# Ethernet_boardv3_09012016.net
KiCad netlist of a schematic drawn in Altium Designer
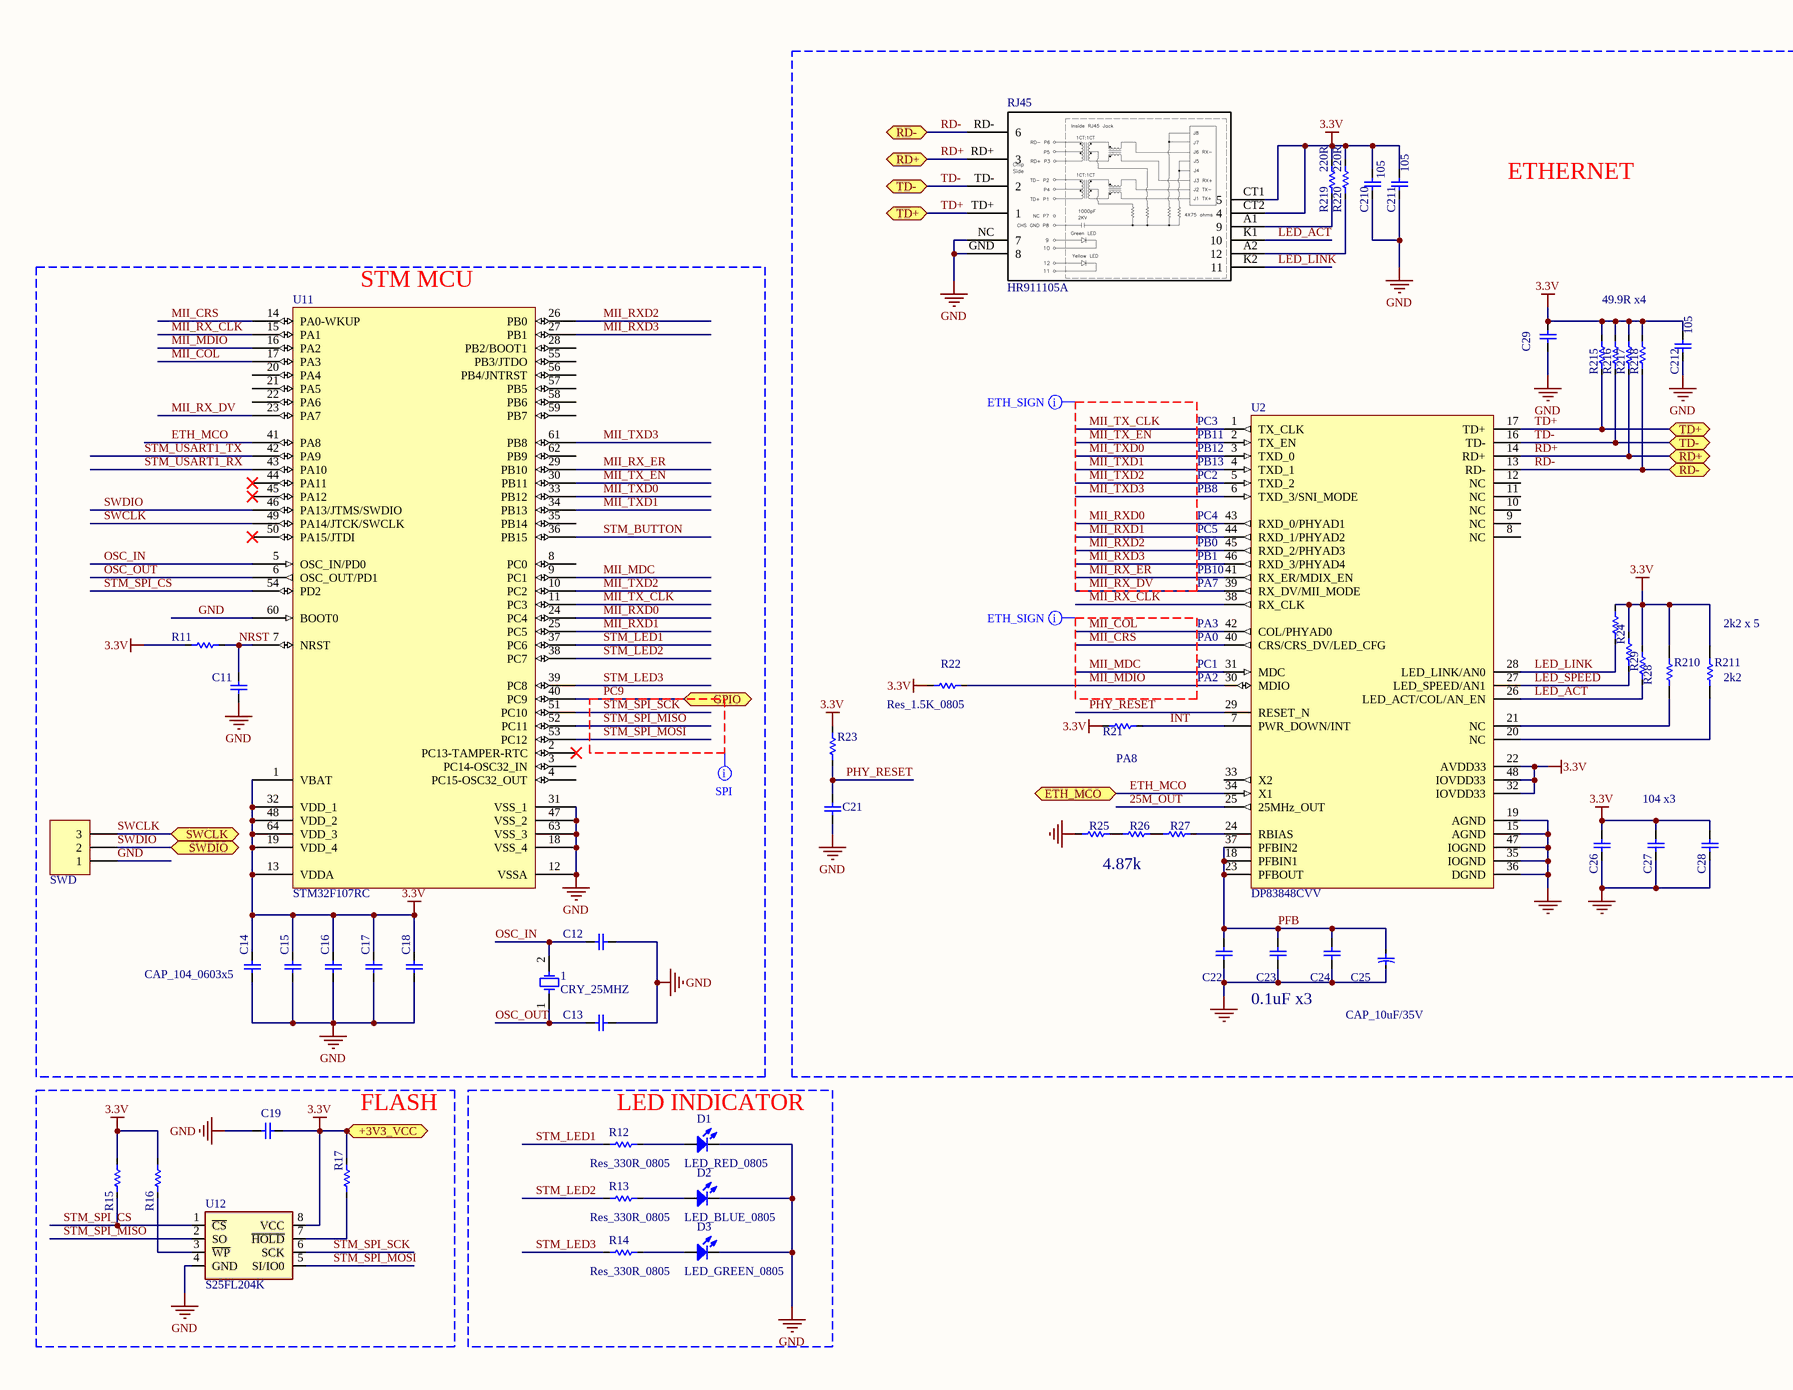
[diagram p0: Ethernet_boardv3_09012016.SchDoc, left]
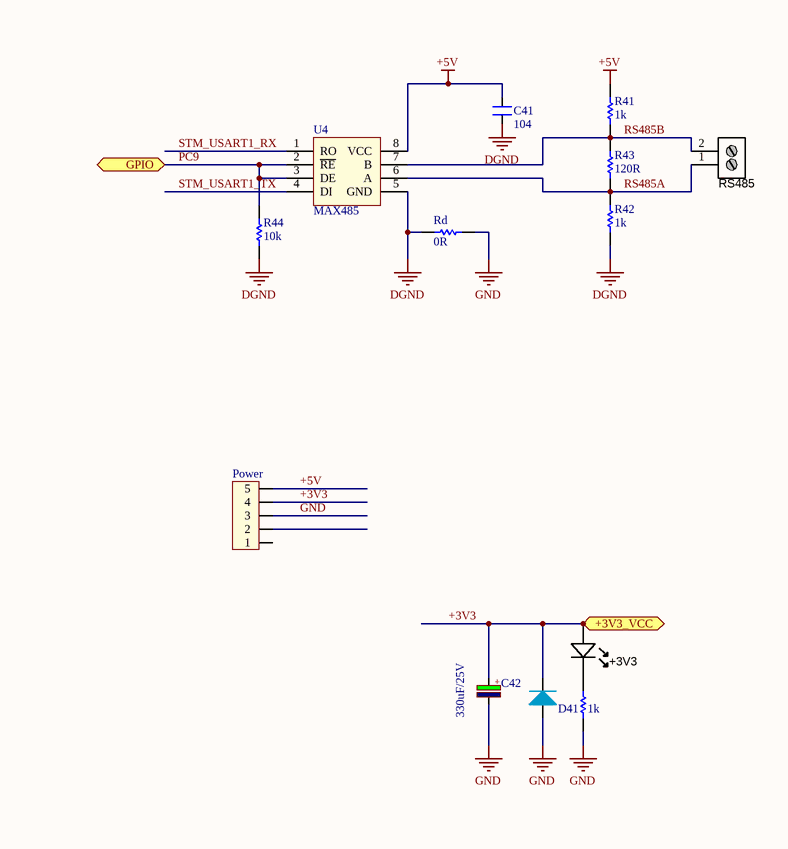
[diagram p1: Ethernet_boardv3_09012016.SchDoc, right]

(export (version "E")
  (design (tool "Eeschema 10.0.6"))
  (components
    (comp (ref "+3V3")
      (value "Blue")
      (footprint "LED-0805-K")
      (description "LED 0805 SMD Blue 100mcd 470nm")
      (libsource (lib "PBL - Light Sources") (part "LED_SMD_Blue_0805_100mcd"))
    )
    (comp (ref "1")
      (value "CRY_25MHZ")
      (footprint "XT2")
      (description "Crystal Oscillator")
      (fields (field (name "PUBLISHER") "Altium Limited"))
      (libsource (lib "THU VIEN CHAN") (part "cry"))
    )
    (comp (ref "C11")
      (value "CAP_102_0603")
      (footprint "CAP_0805_TOP")
      (description "Capacitor")
      (fields (field (name "PUBLISHER") "Altium Limited"))
      (libsource (lib "THU VIEN CHAN") (part "Cap 1206 BUT"))
    )
    (comp (ref "C12")
      (value "CAP_18pF_0603")
      (footprint "CAPC1608N_F")
      (description "Capacitor")
      (fields (field (name "PUBLISHER") "Altium Limited"))
      (libsource (lib "THU VIEN CHAN") (part "Cap 1206 BUT"))
    )
    (comp (ref "C13")
      (value "CAP_18pF_0603")
      (footprint "CAPC1608N_F")
      (description "Capacitor")
      (fields (field (name "PUBLISHER") "Altium Limited"))
      (libsource (lib "THU VIEN CHAN") (part "Cap 1206 BUT"))
    )
    (comp (ref "C14")
      (value "CAP_104_0603")
      (footprint "CAPC1608N_F")
      (description "Capacitor")
      (fields (field (name "PUBLISHER") "Altium Limited"))
      (libsource (lib "THU VIEN CHAN") (part "Cap 1206 BUT"))
    )
    (comp (ref "C15")
      (value "CAP_104_0603")
      (footprint "CAPC1608N_F")
      (description "Capacitor")
      (fields (field (name "PUBLISHER") "Altium Limited"))
      (libsource (lib "THU VIEN CHAN") (part "Cap 1206 BUT"))
    )
    (comp (ref "C16")
      (value "CAP_104_0603")
      (footprint "CAPC1608N_F")
      (description "Capacitor")
      (fields (field (name "PUBLISHER") "Altium Limited"))
      (libsource (lib "THU VIEN CHAN") (part "Cap 1206 BUT"))
    )
    (comp (ref "C17")
      (value "CAP_104_0603")
      (footprint "CAPC1608N_F")
      (description "Capacitor")
      (fields (field (name "PUBLISHER") "Altium Limited"))
      (libsource (lib "THU VIEN CHAN") (part "Cap 1206 BUT"))
    )
    (comp (ref "C18")
      (value "CAP_104_0603")
      (footprint "CAPC1608N_F")
      (description "Capacitor")
      (fields (field (name "PUBLISHER") "Altium Limited"))
      (libsource (lib "THU VIEN CHAN") (part "Cap 1206 BUT"))
    )
    (comp (ref "C19")
      (value "CAP_104_0603")
      (footprint "CAP_0805_TOP")
      (description "Capacitor")
      (fields (field (name "PUBLISHER") "Altium Limited"))
      (libsource (lib "THU VIEN CHAN") (part "Cap 1206 BUT"))
    )
    (comp (ref "C21")
      (value "CAP_102_0603")
      (footprint "CAPC1608N_F")
      (description "Capacitor")
      (fields (field (name "PUBLISHER") "Altium Limited"))
      (libsource (lib "THU VIEN CHAN") (part "Cap 1206 BUT"))
    )
    (comp (ref "C22")
      (value "CAP_104_0603")
      (footprint "CAPC1608N_F")
      (description "Capacitor")
      (fields (field (name "PUBLISHER") "Altium Limited"))
      (libsource (lib "THU VIEN CHAN") (part "Cap 1206 BUT"))
    )
    (comp (ref "C23")
      (value "CAP_104_0603")
      (footprint "CAPC1608N_F")
      (description "Capacitor")
      (fields (field (name "PUBLISHER") "Altium Limited"))
      (libsource (lib "THU VIEN CHAN") (part "Cap 1206 BUT"))
    )
    (comp (ref "C24")
      (value "CAP_104_0603")
      (footprint "CAPC1608N_F")
      (description "Capacitor")
      (fields (field (name "PUBLISHER") "Altium Limited"))
      (libsource (lib "THU VIEN CHAN") (part "Cap 1206 BUT"))
    )
    (comp (ref "C25")
      (value "CAP_10uF/35V")
      (footprint "CAP_10uF/35V")
      (fields (field (name "PUBLISHER") "Altium Limited"))
      (libsource (lib "THU VIEN CHAN") (part "CAP P"))
    )
    (comp (ref "C26")
      (value "CAP_104_0603")
      (footprint "CAPC1608N_F")
      (description "Capacitor")
      (fields (field (name "PUBLISHER") "Altium Limited"))
      (libsource (lib "THU VIEN CHAN") (part "Cap 1206 BUT"))
    )
    (comp (ref "C27")
      (value "CAP_104_0603")
      (footprint "CAPC1608N_F")
      (description "Capacitor")
      (fields (field (name "PUBLISHER") "Altium Limited"))
      (libsource (lib "THU VIEN CHAN") (part "Cap 1206 BUT"))
    )
    (comp (ref "C28")
      (value "CAP_104_0603")
      (footprint "CAPC1608N_F")
      (description "Capacitor")
      (fields (field (name "PUBLISHER") "Altium Limited"))
      (libsource (lib "THU VIEN CHAN") (part "Cap 1206 BUT"))
    )
    (comp (ref "C29")
      (value "CAP_104_0603")
      (footprint "CAPC2012N_F")
      (description "Capacitor")
      (fields (field (name "PUBLISHER") "Altium Limited"))
      (libsource (lib "THU VIEN CHAN") (part "Cap 1206 BUT"))
    )
    (comp (ref "C41")
      (value "104")
      (footprint "CAPC2012N_F")
      (fields (field (name "Comment") "100nF/104"))
      (libsource (lib "Tuan") (part "CAP NP"))
    )
    (comp (ref "C42")
      (value "330uF/25V")
      (footprint "CAPMP3528X210N")
      (description "Cap 1000uF/16V - 220uF/50V")
      (libsource (lib "heromap") (part "CP4"))
    )
    (comp (ref "C210")
      (value "105")
      (footprint "CAPC1608N_F")
      (description "Capacitor")
      (fields (field (name "PUBLISHER") "Altium Limited"))
      (libsource (lib "THU VIEN CHAN") (part "Cap 1206 BUT"))
    )
    (comp (ref "C211")
      (value "105")
      (footprint "CAPC1608N_F")
      (description "Capacitor")
      (fields (field (name "PUBLISHER") "Altium Limited"))
      (libsource (lib "THU VIEN CHAN") (part "Cap 1206 BUT"))
    )
    (comp (ref "C212")
      (value "105")
      (footprint "CAPC2012N_F")
      (description "Capacitor")
      (fields (field (name "PUBLISHER") "Altium Limited"))
      (libsource (lib "THU VIEN CHAN") (part "Cap 1206 BUT"))
    )
    (comp (ref "D1")
      (value "LED_RED_0805")
      (footprint "LED 0805 TOP")
      (description "Typical INFRARED GaAs LED")
      (fields (field (name "PUBLISHER") "Altium Limited"))
      (libsource (lib "THU VIEN CHAN v1") (part "LED 0805 TOP"))
    )
    (comp (ref "D2")
      (value "LED_BLUE_0805")
      (footprint "LED 0805 TOP")
      (description "Typical INFRARED GaAs LED")
      (fields (field (name "PUBLISHER") "Altium Limited"))
      (libsource (lib "THU VIEN CHAN v1") (part "LED 0805 TOP"))
    )
    (comp (ref "D3")
      (value "LED_GREEN_0805")
      (footprint "LED 0805 TOP")
      (description "Typical INFRARED GaAs LED")
      (fields (field (name "PUBLISHER") "Altium Limited"))
      (libsource (lib "THU VIEN CHAN v1") (part "LED 0805 TOP"))
    )
    (comp (ref "D41") (value "Diode") (footprint "DO-214AC") (libsource (lib "Tuan") (part "Diode")))
    (comp (ref "Power")
      (value "JP5")
      (footprint "heromap:CON5")
      (description "Connector 5")
      (libsource (lib "heromap") (part "Con5"))
    )
    (comp (ref "R11")
      (value "Res_4.7K_0805")
      (footprint "RES_0805_TOP")
      (description "Resistor")
      (fields (field (name "PUBLISHER") "Altium Limited"))
      (libsource (lib "THU VIEN CHAN") (part "Res"))
    )
    (comp (ref "R12")
      (value "Res_330R_0805")
      (footprint "RES_0805_TOP")
      (description "Resistor")
      (fields (field (name "PUBLISHER") "Altium Limited"))
      (libsource (lib "THU VIEN CHAN") (part "Res"))
    )
    (comp (ref "R13")
      (value "Res_330R_0805")
      (footprint "RES_0805_TOP")
      (description "Resistor")
      (fields (field (name "PUBLISHER") "Altium Limited"))
      (libsource (lib "THU VIEN CHAN") (part "Res"))
    )
    (comp (ref "R14")
      (value "Res_330R_0805")
      (footprint "RES_0805_TOP")
      (description "Resistor")
      (fields (field (name "PUBLISHER") "Altium Limited"))
      (libsource (lib "THU VIEN CHAN") (part "Res"))
    )
    (comp (ref "R15")
      (value "Res_4.7K_0805")
      (footprint "RES_0805_TOP")
      (description "Resistor")
      (fields (field (name "PUBLISHER") "Altium Limited"))
      (libsource (lib "THU VIEN CHAN") (part "Res"))
    )
    (comp (ref "R16")
      (value "Res_4.7K_0805")
      (footprint "RES_0805_TOP")
      (description "Resistor")
      (fields (field (name "PUBLISHER") "Altium Limited"))
      (libsource (lib "THU VIEN CHAN") (part "Res"))
    )
    (comp (ref "R17")
      (value "Res_4.7K_0805")
      (footprint "RES_0805_TOP")
      (description "Resistor")
      (fields (field (name "PUBLISHER") "Altium Limited"))
      (libsource (lib "THU VIEN CHAN") (part "Res"))
    )
    (comp (ref "R21")
      (value "Res_2.2K_0805")
      (footprint "RESC1608N_F")
      (description "Resistor")
      (fields (field (name "PUBLISHER") "Altium Limited"))
      (libsource (lib "THU VIEN CHAN") (part "Res"))
    )
    (comp (ref "R22")
      (value "Res_1.5K_0805")
      (footprint "RESC1608N_F")
      (description "Resistor")
      (fields (field (name "PUBLISHER") "Altium Limited"))
      (libsource (lib "") (part "Res_1"))
    )
    (comp (ref "R23")
      (value "Res_4.7K_0805")
      (footprint "RESC1608N_F")
      (description "Resistor")
      (fields (field (name "PUBLISHER") "Altium Limited"))
      (libsource (lib "") (part "Res_1"))
    )
    (comp (ref "R24")
      (value "Res_2.2K_0805")
      (footprint "RESC1608N_F")
      (description "Resistor")
      (fields (field (name "PUBLISHER") "Altium Limited"))
      (libsource (lib "THU VIEN CHAN") (part "Res"))
    )
    (comp (ref "R25")
      (value "Res_47R_0805")
      (footprint "RES_0805_TOP")
      (description "Resistor")
      (fields (field (name "PUBLISHER") "Altium Limited"))
      (libsource (lib "THU VIEN CHAN") (part "Res"))
    )
    (comp (ref "R26")
      (value "Res_120R_0805")
      (footprint "RES_0805_TOP")
      (description "Resistor")
      (fields (field (name "PUBLISHER") "Altium Limited"))
      (libsource (lib "THU VIEN CHAN") (part "Res"))
    )
    (comp (ref "R27")
      (value "Res_4.7K_0805")
      (footprint "RES_0805_TOP")
      (description "Resistor")
      (fields (field (name "PUBLISHER") "Altium Limited"))
      (libsource (lib "THU VIEN CHAN") (part "Res"))
    )
    (comp (ref "R28")
      (value "Res_0R_0603")
      (footprint "RESC1608N_F")
      (description "Resistor")
      (fields (field (name "PUBLISHER") "Altium Limited"))
      (libsource (lib "THU VIEN CHAN") (part "Res"))
    )
    (comp (ref "R29")
      (value "Res_0R_0603")
      (footprint "RESC1608N_F")
      (description "Resistor")
      (fields (field (name "PUBLISHER") "Altium Limited"))
      (libsource (lib "THU VIEN CHAN") (part "Res"))
    )
    (comp (ref "R41")
      (value "1k")
      (footprint "RESC2012N_F")
      (description "Tro dan")
      (libsource (lib "GPS_Clock_v12") (part "Res"))
    )
    (comp (ref "R42")
      (value "1k")
      (footprint "RESC2012N_F")
      (description "Tro dan")
      (libsource (lib "GPS_Clock_v12") (part "Res"))
    )
    (comp (ref "R43")
      (value "120R")
      (footprint "RESC2012N_F")
      (description "Tro dan")
      (fields (field (name "Comment") "330R"))
      (libsource (lib "GPS_Clock_v12") (part "Res"))
    )
    (comp (ref "R44")
      (value "10k")
      (footprint "RESC2012N_F")
      (description "Tro dan")
      (fields (field (name "Comment") "330R"))
      (libsource (lib "GPS_Clock_v12") (part "Res"))
    )
    (comp (ref "R210") (value "2k2") (footprint "RESC1608N_F") (libsource (lib "Tuan") (part "Res")))
    (comp (ref "R211") (value "2k2") (footprint "RESC1608N_F") (libsource (lib "Tuan") (part "Res")))
    (comp (ref "R215")
      (value "Res_49.9R_0805")
      (footprint "RES_0805_TOP")
      (description "Resistor")
      (fields (field (name "PUBLISHER") "Altium Limited"))
      (libsource (lib "THU VIEN CHAN") (part "Res"))
    )
    (comp (ref "R216")
      (value "Res_49.9R_0805")
      (footprint "RES_0805_TOP")
      (description "Resistor")
      (fields (field (name "PUBLISHER") "Altium Limited"))
      (libsource (lib "THU VIEN CHAN") (part "Res"))
    )
    (comp (ref "R217")
      (value "Res_49.9R_0805")
      (footprint "RES_0805_TOP")
      (description "Resistor")
      (fields (field (name "PUBLISHER") "Altium Limited"))
      (libsource (lib "THU VIEN CHAN") (part "Res"))
    )
    (comp (ref "R218")
      (value "Res_49.9R_0805")
      (footprint "RES_0805_TOP")
      (description "Resistor")
      (fields (field (name "PUBLISHER") "Altium Limited"))
      (libsource (lib "THU VIEN CHAN") (part "Res"))
    )
    (comp (ref "R219")
      (value "220R")
      (footprint "RESC1608N_F")
      (description "Resistor")
      (fields (field (name "PUBLISHER") "Altium Limited"))
      (libsource (lib "THU VIEN CHAN") (part "Res"))
    )
    (comp (ref "R220")
      (value "220R")
      (footprint "RESC1608N_F")
      (description "Resistor")
      (fields (field (name "PUBLISHER") "Altium Limited"))
      (libsource (lib "THU VIEN CHAN") (part "Res"))
    )
    (comp (ref "Rd")
      (value "0R")
      (footprint "RESC2012N_F")
      (fields (field (name "Comment") "Res"))
      (libsource (lib "Tuan") (part "Res"))
    )
    (comp (ref "RJ45") (value "HR911105A") (footprint "HR911105A") (libsource (lib "Tuan") (part "RJ45-LED")))
    (comp (ref "Rled")
      (value "1k")
      (footprint "RESC2012N_F")
      (fields (field (name "Comment") "Res_0805_1k"))
      (libsource (lib "Tuan") (part "Res"))
    )
    (comp (ref "RS485")
      (value "Stackable ScrewTerm")
      (footprint "2P_PCB1")
      (description "Terminal Block Screw Type THT 2-Position 3.81mm pitch")
      (libsource (lib "PBL - Connectors") (part "2P_ScrewTerm_90S_3.81MM"))
    )
    (comp (ref "SWD")
      (value "Header 3")
      (footprint "heromap:HDR1X3")
      (description "Header, 3-Pin")
      (fields (field (name "PUBLISHER") "Altium Limited"))
      (libsource (lib "heromap") (part "Header 3"))
    )
    (comp (ref "U2")
      (value "DP83848CVV")
      (footprint "LQFP48")
      (libsource (lib "THU VIEN CHAN v1") (part "DP83848CVV"))
    )
    (comp (ref "U4")
      (value "MAX485")
      (footprint "SO-8")
      (description "RS232 - RS485 (Same sn75176)")
      (libsource (lib "heromap") (part "MAX485"))
    )
    (comp (ref "U11")
      (value "STM32F107RC")
      (footprint "LQFP64_N")
      (description "STM32 ARM-based 32-bit MCU with 128 Kbytes Flash, 64-pin LQFP, Industrial Temperature")
      (fields (field (name "PUBLISHER") "Altium Limited"))
      (libsource (lib "ST Microcontroller 32-Bit STM32") (part "STM32F103RBT6"))
    )
    (comp (ref "U12")
      (value "S25FL204K")
      (footprint "SOIC_8")
      (libsource (lib "THU VIEN CHAN v1") (part "S25FL204K"))
    )
  )
  (nets
    (net (code "1") (name "+5V") (class "Default")
      (node (ref "C41") (pin "2") (pinfunction "2_2") (pintype "passive"))
      (node (ref "Power") (pin "5") (pinfunction "5_5") (pintype "passive"))
      (node (ref "R41") (pin "2") (pinfunction "2_2") (pintype "passive"))
      (node (ref "U4") (pin "8") (pinfunction "VCC_8") (pintype "passive"))
    )
    (net (code "2") (name "/25M_OUT") (class "Default")
      (node (ref "U2") (pin "25") (pinfunction "25MHz_OUT_25") (pintype "output"))
    )
    (net (code "3") (name "/ETH_MCO") (class "Default")
      (node (ref "U11") (pin "41") (pinfunction "PA8_41") (pintype "bidirectional"))
      (node (ref "U2") (pin "34") (pinfunction "X1_34") (pintype "input"))
    )
    (net (code "4") (name "/INT") (class "Default")
      (node (ref "R21") (pin "1") (pinfunction "1_1") (pintype "passive"))
      (node (ref "U2") (pin "7") (pinfunction "PWR_DOWN/INT_7") (pintype "passive"))
    )
    (net (code "5") (name "/LED_ACT") (class "Default")
      (node (ref "R28") (pin "2") (pinfunction "2_2") (pintype "passive"))
      (node (ref "RJ45") (pin "K1") (pinfunction "10_K1") (pintype "passive"))
      (node (ref "U2") (pin "26") (pinfunction "LED_ACT/COL/AN_EN_26") (pintype "passive"))
    )
    (net (code "6") (name "/LED_LINK") (class "Default")
      (node (ref "R24") (pin "1") (pinfunction "1_1") (pintype "passive"))
      (node (ref "RJ45") (pin "K2") (pinfunction "11_K2") (pintype "passive"))
      (node (ref "U2") (pin "28") (pinfunction "LED_LINK/AN0_28") (pintype "passive"))
    )
    (net (code "7") (name "/LED_SPEED") (class "Default")
      (node (ref "R29") (pin "1") (pinfunction "1_1") (pintype "passive"))
      (node (ref "U2") (pin "27") (pinfunction "LED_SPEED/AN1_27") (pintype "passive"))
    )
    (net (code "8") (name "/MII_COL") (class "Default")
      (node (ref "U11") (pin "17") (pinfunction "PA3_17") (pintype "bidirectional"))
      (node (ref "U2") (pin "42") (pinfunction "COL/PHYAD0_42") (pintype "output"))
    )
    (net (code "9") (name "/MII_CRS") (class "Default")
      (node (ref "U11") (pin "14") (pinfunction "PA0-WKUP_14") (pintype "bidirectional"))
      (node (ref "U2") (pin "40") (pinfunction "CRS/CRS_DV/LED_CFG_40") (pintype "output"))
    )
    (net (code "10") (name "/MII_MDC") (class "Default")
      (node (ref "U11") (pin "9") (pinfunction "PC1_9") (pintype "bidirectional"))
      (node (ref "U2") (pin "31") (pinfunction "MDC_31") (pintype "input"))
    )
    (net (code "11") (name "/MII_MDIO") (class "Default")
      (node (ref "R22") (pin "2") (pinfunction "2_2") (pintype "passive"))
      (node (ref "U11") (pin "16") (pinfunction "PA2_16") (pintype "bidirectional"))
      (node (ref "U2") (pin "30") (pinfunction "MDIO_30") (pintype "bidirectional"))
    )
    (net (code "12") (name "/MII_RXD0") (class "Default")
      (node (ref "U11") (pin "24") (pinfunction "PC4_24") (pintype "bidirectional"))
      (node (ref "U2") (pin "43") (pinfunction "RXD_0/PHYAD1_43") (pintype "output"))
    )
    (net (code "13") (name "/MII_RXD1") (class "Default")
      (node (ref "U11") (pin "25") (pinfunction "PC5_25") (pintype "bidirectional"))
      (node (ref "U2") (pin "44") (pinfunction "RXD_1/PHYAD2_44") (pintype "output"))
    )
    (net (code "14") (name "/MII_RXD2") (class "Default")
      (node (ref "U11") (pin "26") (pinfunction "PB0_26") (pintype "bidirectional"))
      (node (ref "U2") (pin "45") (pinfunction "RXD_2/PHYAD3_45") (pintype "output"))
    )
    (net (code "15") (name "/MII_RXD3") (class "Default")
      (node (ref "U11") (pin "27") (pinfunction "PB1_27") (pintype "bidirectional"))
      (node (ref "U2") (pin "46") (pinfunction "RXD_3/PHYAD4_46") (pintype "output"))
    )
    (net (code "16") (name "/MII_RX_CLK") (class "Default")
      (node (ref "U11") (pin "15") (pinfunction "PA1_15") (pintype "bidirectional"))
      (node (ref "U2") (pin "38") (pinfunction "RX_CLK_38") (pintype "output"))
    )
    (net (code "17") (name "/MII_RX_DV") (class "Default")
      (node (ref "U11") (pin "23") (pinfunction "PA7_23") (pintype "bidirectional"))
      (node (ref "U2") (pin "39") (pinfunction "RX_DV/MII_MODE_39") (pintype "output"))
    )
    (net (code "18") (name "/MII_RX_ER") (class "Default")
      (node (ref "U11") (pin "29") (pinfunction "PB10_29") (pintype "bidirectional"))
      (node (ref "U2") (pin "41") (pinfunction "RX_ER/MDIX_EN_41") (pintype "output"))
    )
    (net (code "19") (name "/MII_TXD0") (class "Default")
      (node (ref "U11") (pin "33") (pinfunction "PB12_33") (pintype "bidirectional"))
      (node (ref "U2") (pin "3") (pinfunction "TXD_0_3") (pintype "input"))
    )
    (net (code "20") (name "/MII_TXD1") (class "Default")
      (node (ref "U11") (pin "34") (pinfunction "PB13_34") (pintype "bidirectional"))
      (node (ref "U2") (pin "4") (pinfunction "TXD_1_4") (pintype "input"))
    )
    (net (code "21") (name "/MII_TXD2") (class "Default")
      (node (ref "U11") (pin "10") (pinfunction "PC2_10") (pintype "bidirectional"))
      (node (ref "U2") (pin "5") (pinfunction "TXD_2_5") (pintype "input"))
    )
    (net (code "22") (name "/MII_TXD3") (class "Default")
      (node (ref "U11") (pin "61") (pinfunction "PB8_61") (pintype "bidirectional"))
      (node (ref "U2") (pin "6") (pinfunction "TXD_3/SNI_MODE_6") (pintype "input"))
    )
    (net (code "23") (name "/MII_TX_CLK") (class "Default")
      (node (ref "U11") (pin "11") (pinfunction "PC3_11") (pintype "bidirectional"))
      (node (ref "U2") (pin "1") (pinfunction "TX_CLK_1") (pintype "output"))
    )
    (net (code "24") (name "/MII_TX_EN") (class "Default")
      (node (ref "U11") (pin "30") (pinfunction "PB11_30") (pintype "bidirectional"))
      (node (ref "U2") (pin "2") (pinfunction "TX_EN_2") (pintype "input"))
    )
    (net (code "25") (name "/NRST") (class "Default")
      (node (ref "C11") (pin "1") (pinfunction "1_1") (pintype "passive"))
      (node (ref "R11") (pin "1") (pinfunction "1_1") (pintype "passive"))
      (node (ref "U11") (pin "7") (pinfunction "NRST_7") (pintype "bidirectional"))
    )
    (net (code "26") (name "/OSC_IN") (class "Default")
      (node (ref "1") (pin "2") (pinfunction "OSC2_2") (pintype "passive"))
      (node (ref "C12") (pin "1") (pinfunction "1_1") (pintype "passive"))
      (node (ref "U11") (pin "5") (pinfunction "OSC_IN/PD0_5") (pintype "input"))
    )
    (net (code "27") (name "/OSC_OUT") (class "Default")
      (node (ref "1") (pin "1") (pinfunction "OSC1_1") (pintype "passive"))
      (node (ref "C13") (pin "1") (pinfunction "1_1") (pintype "passive"))
      (node (ref "U11") (pin "6") (pinfunction "OSC_OUT/PD1_6") (pintype "output"))
    )
    (net (code "28") (name "/PC9") (class "Default")
      (node (ref "R44") (pin "2") (pinfunction "2_2") (pintype "passive"))
      (node (ref "U11") (pin "40") (pinfunction "PC9_40") (pintype "bidirectional"))
      (node (ref "U4") (pin "2") (pinfunction "~{RE}_2") (pintype "passive"))
      (node (ref "U4") (pin "3") (pinfunction "DE_3") (pintype "passive"))
    )
    (net (code "29") (name "/PFB") (class "Default")
      (node (ref "C22") (pin "2") (pinfunction "2_2") (pintype "passive"))
      (node (ref "C23") (pin "2") (pinfunction "2_2") (pintype "passive"))
      (node (ref "C24") (pin "2") (pinfunction "2_2") (pintype "passive"))
      (node (ref "C25") (pin "1") (pinfunction "1_1") (pintype "passive"))
      (node (ref "U2") (pin "18") (pinfunction "PFBIN1_18") (pintype "passive"))
      (node (ref "U2") (pin "23") (pinfunction "PFBOUT_23") (pintype "passive"))
      (node (ref "U2") (pin "37") (pinfunction "PFBIN2_37") (pintype "passive"))
    )
    (net (code "30") (name "/PHY_RESET") (class "Default")
      (node (ref "C21") (pin "2") (pinfunction "2_2") (pintype "passive"))
      (node (ref "R23") (pin "1") (pinfunction "1_1") (pintype "passive"))
      (node (ref "U2") (pin "29") (pinfunction "RESET_N_29") (pintype "passive"))
    )
    (net (code "31") (name "/RD+") (class "Default")
      (node (ref "R217") (pin "2") (pinfunction "2_2") (pintype "passive"))
      (node (ref "RJ45") (pin "RD+") (pinfunction "3_RD+") (pintype "passive"))
      (node (ref "U2") (pin "14") (pinfunction "RD+_14") (pintype "passive"))
    )
    (net (code "32") (name "/RD-") (class "Default")
      (node (ref "R218") (pin "2") (pinfunction "2_2") (pintype "passive"))
      (node (ref "RJ45") (pin "RD-") (pinfunction "6_RD-") (pintype "passive"))
      (node (ref "U2") (pin "13") (pinfunction "RD-_13") (pintype "passive"))
    )
    (net (code "33") (name "/RS485A") (class "Default")
      (node (ref "R42") (pin "2") (pinfunction "2_2") (pintype "passive"))
      (node (ref "R43") (pin "1") (pinfunction "1_1") (pintype "passive"))
      (node (ref "RS485") (pin "1") (pinfunction "1_1") (pintype "passive"))
      (node (ref "U4") (pin "6") (pinfunction "A_6") (pintype "passive"))
    )
    (net (code "34") (name "/RS485B") (class "Default")
      (node (ref "R41") (pin "1") (pinfunction "1_1") (pintype "passive"))
      (node (ref "R43") (pin "2") (pinfunction "2_2") (pintype "passive"))
      (node (ref "RS485") (pin "2") (pinfunction "2_2") (pintype "passive"))
      (node (ref "U4") (pin "7") (pinfunction "B_7") (pintype "passive"))
    )
    (net (code "35") (name "/STM_BUTTON") (class "Default")
      (node (ref "U11") (pin "36") (pinfunction "PB15_36") (pintype "bidirectional"))
    )
    (net (code "36") (name "/STM_LED1") (class "Default")
      (node (ref "R12") (pin "1") (pinfunction "1_1") (pintype "passive"))
      (node (ref "U11") (pin "37") (pinfunction "PC6_37") (pintype "bidirectional"))
    )
    (net (code "37") (name "/STM_LED2") (class "Default")
      (node (ref "R13") (pin "1") (pinfunction "1_1") (pintype "passive"))
      (node (ref "U11") (pin "38") (pinfunction "PC7_38") (pintype "bidirectional"))
    )
    (net (code "38") (name "/STM_LED3") (class "Default")
      (node (ref "R14") (pin "1") (pinfunction "1_1") (pintype "passive"))
      (node (ref "U11") (pin "39") (pinfunction "PC8_39") (pintype "bidirectional"))
    )
    (net (code "39") (name "/STM_SPI_CS") (class "Default")
      (node (ref "R15") (pin "2") (pinfunction "2_2") (pintype "passive"))
      (node (ref "U11") (pin "54") (pinfunction "PD2_54") (pintype "bidirectional"))
      (node (ref "U12") (pin "1") (pinfunction "~{CS}_1") (pintype "passive"))
    )
    (net (code "40") (name "/STM_SPI_MISO") (class "Default")
      (node (ref "U11") (pin "52") (pinfunction "PC11_52") (pintype "bidirectional"))
      (node (ref "U12") (pin "2") (pinfunction "SO_2") (pintype "passive"))
    )
    (net (code "41") (name "/STM_SPI_MOSI") (class "Default")
      (node (ref "U11") (pin "53") (pinfunction "PC12_53") (pintype "bidirectional"))
      (node (ref "U12") (pin "5") (pinfunction "SI/IO0_5") (pintype "passive"))
    )
    (net (code "42") (name "/STM_SPI_SCK") (class "Default")
      (node (ref "U11") (pin "51") (pinfunction "PC10_51") (pintype "bidirectional"))
      (node (ref "U12") (pin "6") (pinfunction "SCK_6") (pintype "passive"))
    )
    (net (code "43") (name "/STM_USART1_RX") (class "Default")
      (node (ref "U11") (pin "43") (pinfunction "PA10_43") (pintype "bidirectional"))
      (node (ref "U4") (pin "1") (pinfunction "RO_1") (pintype "passive"))
    )
    (net (code "44") (name "/STM_USART1_TX") (class "Default")
      (node (ref "U11") (pin "42") (pinfunction "PA9_42") (pintype "bidirectional"))
      (node (ref "U4") (pin "4") (pinfunction "DI_4") (pintype "passive"))
    )
    (net (code "45") (name "/SWCLK") (class "Default")
      (node (ref "SWD") (pin "3") (pinfunction "3_3") (pintype "passive"))
      (node (ref "U11") (pin "49") (pinfunction "PA14/JTCK/SWCLK_49") (pintype "bidirectional"))
    )
    (net (code "46") (name "/SWDIO") (class "Default")
      (node (ref "SWD") (pin "2") (pinfunction "2_2") (pintype "passive"))
      (node (ref "U11") (pin "46") (pinfunction "PA13/JTMS/SWDIO_46") (pintype "bidirectional"))
    )
    (net (code "47") (name "/TD+") (class "Default")
      (node (ref "R215") (pin "2") (pinfunction "2_2") (pintype "passive"))
      (node (ref "RJ45") (pin "TD+") (pinfunction "1_TD+") (pintype "passive"))
      (node (ref "U2") (pin "17") (pinfunction "TD+_17") (pintype "passive"))
    )
    (net (code "48") (name "/TD-") (class "Default")
      (node (ref "R216") (pin "2") (pinfunction "2_2") (pintype "passive"))
      (node (ref "RJ45") (pin "TD-") (pinfunction "2_TD-") (pintype "passive"))
      (node (ref "U2") (pin "16") (pinfunction "TD-_16") (pintype "passive"))
    )
    (net (code "49") (name "3.3V") (class "Default")
      (node (ref "+3V3") (pin "A") (pinfunction "A_A") (pintype "passive"))
      (node (ref "C14") (pin "1") (pinfunction "1_1") (pintype "passive"))
      (node (ref "C15") (pin "1") (pinfunction "1_1") (pintype "passive"))
      (node (ref "C16") (pin "1") (pinfunction "1_1") (pintype "passive"))
      (node (ref "C17") (pin "1") (pinfunction "1_1") (pintype "passive"))
      (node (ref "C18") (pin "1") (pinfunction "1_1") (pintype "passive"))
      (node (ref "C19") (pin "1") (pinfunction "1_1") (pintype "passive"))
      (node (ref "C210") (pin "1") (pinfunction "1_1") (pintype "passive"))
      (node (ref "C211") (pin "1") (pinfunction "1_1") (pintype "passive"))
      (node (ref "C212") (pin "1") (pinfunction "1_1") (pintype "passive"))
      (node (ref "C26") (pin "2") (pinfunction "2_2") (pintype "passive"))
      (node (ref "C27") (pin "1") (pinfunction "1_1") (pintype "passive"))
      (node (ref "C28") (pin "2") (pinfunction "2_2") (pintype "passive"))
      (node (ref "C29") (pin "1") (pinfunction "1_1") (pintype "passive"))
      (node (ref "C42") (pin "1") (pinfunction "1_1") (pintype "passive"))
      (node (ref "D41") (pin "2") (pinfunction "K_2") (pintype "passive"))
      (node (ref "Power") (pin "4") (pinfunction "4_4") (pintype "passive"))
      (node (ref "R11") (pin "2") (pinfunction "2_2") (pintype "passive"))
      (node (ref "R15") (pin "1") (pinfunction "1_1") (pintype "passive"))
      (node (ref "R16") (pin "1") (pinfunction "1_1") (pintype "passive"))
      (node (ref "R17") (pin "1") (pinfunction "1_1") (pintype "passive"))
      (node (ref "R21") (pin "2") (pinfunction "2_2") (pintype "passive"))
      (node (ref "R210") (pin "2") (pinfunction "2_2") (pintype "passive"))
      (node (ref "R211") (pin "2") (pinfunction "2_2") (pintype "passive"))
      (node (ref "R215") (pin "1") (pinfunction "1_1") (pintype "passive"))
      (node (ref "R216") (pin "1") (pinfunction "1_1") (pintype "passive"))
      (node (ref "R217") (pin "1") (pinfunction "1_1") (pintype "passive"))
      (node (ref "R218") (pin "1") (pinfunction "1_1") (pintype "passive"))
      (node (ref "R219") (pin "1") (pinfunction "1_1") (pintype "passive"))
      (node (ref "R22") (pin "1") (pinfunction "1_1") (pintype "passive"))
      (node (ref "R220") (pin "1") (pinfunction "1_1") (pintype "passive"))
      (node (ref "R23") (pin "2") (pinfunction "2_2") (pintype "passive"))
      (node (ref "R24") (pin "2") (pinfunction "2_2") (pintype "passive"))
      (node (ref "R28") (pin "1") (pinfunction "1_1") (pintype "passive"))
      (node (ref "R29") (pin "2") (pinfunction "2_2") (pintype "passive"))
      (node (ref "RJ45") (pin "CT1") (pinfunction "5_CT1") (pintype "passive"))
      (node (ref "RJ45") (pin "CT2") (pinfunction "4_CT2") (pintype "passive"))
      (node (ref "U11") (pin "1") (pinfunction "VBAT_1") (pintype "power_in"))
      (node (ref "U11") (pin "13") (pinfunction "VDDA_13") (pintype "power_in"))
      (node (ref "U11") (pin "19") (pinfunction "VDD_4_19") (pintype "power_in"))
      (node (ref "U11") (pin "32") (pinfunction "VDD_1_32") (pintype "power_in"))
      (node (ref "U11") (pin "48") (pinfunction "VDD_2_48") (pintype "power_in"))
      (node (ref "U11") (pin "64") (pinfunction "VDD_3_64") (pintype "power_in"))
      (node (ref "U12") (pin "8") (pinfunction "VCC_8") (pintype "passive"))
      (node (ref "U2") (pin "22") (pinfunction "AVDD33_22") (pintype "passive"))
      (node (ref "U2") (pin "32") (pinfunction "IOVDD33_32") (pintype "passive"))
      (node (ref "U2") (pin "48") (pinfunction "IOVDD33_48") (pintype "passive"))
    )
    (net (code "50") (name "DGND") (class "Default")
      (node (ref "C41") (pin "1") (pinfunction "1_1") (pintype "passive"))
      (node (ref "R42") (pin "1") (pinfunction "1_1") (pintype "passive"))
      (node (ref "R44") (pin "1") (pinfunction "1_1") (pintype "passive"))
      (node (ref "Rd") (pin "1") (pinfunction "1_1") (pintype "passive"))
      (node (ref "U4") (pin "5") (pinfunction "GND_5") (pintype "passive"))
    )
    (net (code "51") (name "GND") (class "Default")
      (node (ref "C11") (pin "2") (pinfunction "2_2") (pintype "passive"))
      (node (ref "C12") (pin "2") (pinfunction "2_2") (pintype "passive"))
      (node (ref "C13") (pin "2") (pinfunction "2_2") (pintype "passive"))
      (node (ref "C14") (pin "2") (pinfunction "2_2") (pintype "passive"))
      (node (ref "C15") (pin "2") (pinfunction "2_2") (pintype "passive"))
      (node (ref "C16") (pin "2") (pinfunction "2_2") (pintype "passive"))
      (node (ref "C17") (pin "2") (pinfunction "2_2") (pintype "passive"))
      (node (ref "C18") (pin "2") (pinfunction "2_2") (pintype "passive"))
      (node (ref "C19") (pin "2") (pinfunction "2_2") (pintype "passive"))
      (node (ref "C21") (pin "1") (pinfunction "1_1") (pintype "passive"))
      (node (ref "C210") (pin "2") (pinfunction "2_2") (pintype "passive"))
      (node (ref "C211") (pin "2") (pinfunction "2_2") (pintype "passive"))
      (node (ref "C212") (pin "2") (pinfunction "2_2") (pintype "passive"))
      (node (ref "C22") (pin "1") (pinfunction "1_1") (pintype "passive"))
      (node (ref "C23") (pin "1") (pinfunction "1_1") (pintype "passive"))
      (node (ref "C24") (pin "1") (pinfunction "1_1") (pintype "passive"))
      (node (ref "C25") (pin "2") (pinfunction "2_2") (pintype "passive"))
      (node (ref "C26") (pin "1") (pinfunction "1_1") (pintype "passive"))
      (node (ref "C27") (pin "2") (pinfunction "2_2") (pintype "passive"))
      (node (ref "C28") (pin "1") (pinfunction "1_1") (pintype "passive"))
      (node (ref "C29") (pin "2") (pinfunction "2_2") (pintype "passive"))
      (node (ref "C42") (pin "2") (pinfunction "2_2") (pintype "passive"))
      (node (ref "D1") (pin "2") (pinfunction "K_2") (pintype "passive"))
      (node (ref "D2") (pin "2") (pinfunction "K_2") (pintype "passive"))
      (node (ref "D3") (pin "2") (pinfunction "K_2") (pintype "passive"))
      (node (ref "D41") (pin "1") (pinfunction "A_1") (pintype "passive"))
      (node (ref "Power") (pin "3") (pinfunction "3_3") (pintype "passive"))
      (node (ref "R25") (pin "2") (pinfunction "2_2") (pintype "passive"))
      (node (ref "RJ45") (pin "GND") (pinfunction "8_GND") (pintype "passive"))
      (node (ref "RJ45") (pin "NC") (pinfunction "7_NC") (pintype "passive"))
      (node (ref "Rd") (pin "2") (pinfunction "2_2") (pintype "passive"))
      (node (ref "Rled") (pin "2") (pinfunction "2_2") (pintype "passive"))
      (node (ref "SWD") (pin "1") (pinfunction "1_1") (pintype "passive"))
      (node (ref "U11") (pin "12") (pinfunction "VSSA_12") (pintype "power_in"))
      (node (ref "U11") (pin "18") (pinfunction "VSS_4_18") (pintype "power_in"))
      (node (ref "U11") (pin "31") (pinfunction "VSS_1_31") (pintype "power_in"))
      (node (ref "U11") (pin "47") (pinfunction "VSS_2_47") (pintype "power_in"))
      (node (ref "U11") (pin "60") (pinfunction "BOOT0_60") (pintype "input"))
      (node (ref "U11") (pin "63") (pinfunction "VSS_3_63") (pintype "power_in"))
      (node (ref "U12") (pin "4") (pinfunction "GND_4") (pintype "passive"))
      (node (ref "U2") (pin "15") (pinfunction "AGND_15") (pintype "passive"))
      (node (ref "U2") (pin "19") (pinfunction "AGND_19") (pintype "passive"))
      (node (ref "U2") (pin "35") (pinfunction "IOGND_35") (pintype "passive"))
      (node (ref "U2") (pin "36") (pinfunction "DGND_36") (pintype "passive"))
      (node (ref "U2") (pin "47") (pinfunction "IOGND_47") (pintype "passive"))
    )
    (net (code "52") (name "Net-(+3V3-PadK)") (class "Default")
      (node (ref "+3V3") (pin "K") (pinfunction "K_K") (pintype "passive"))
      (node (ref "Rled") (pin "1") (pinfunction "1_1") (pintype "passive"))
    )
    (net (code "53") (name "Net-(D1-A)") (class "Default")
      (node (ref "D1") (pin "1") (pinfunction "A_1") (pintype "passive"))
      (node (ref "R12") (pin "2") (pinfunction "2_2") (pintype "passive"))
    )
    (net (code "54") (name "Net-(D2-A)") (class "Default")
      (node (ref "D2") (pin "1") (pinfunction "A_1") (pintype "passive"))
      (node (ref "R13") (pin "2") (pinfunction "2_2") (pintype "passive"))
    )
    (net (code "55") (name "Net-(D3-A)") (class "Default")
      (node (ref "D3") (pin "1") (pinfunction "A_1") (pintype "passive"))
      (node (ref "R14") (pin "2") (pinfunction "2_2") (pintype "passive"))
    )
    (net (code "56") (name "Net-(R25-Pad1)") (class "Default")
      (node (ref "R25") (pin "1") (pinfunction "1_1") (pintype "passive"))
      (node (ref "R26") (pin "1") (pinfunction "1_1") (pintype "passive"))
    )
    (net (code "57") (name "Net-(R26-Pad2)") (class "Default")
      (node (ref "R26") (pin "2") (pinfunction "2_2") (pintype "passive"))
      (node (ref "R27") (pin "2") (pinfunction "2_2") (pintype "passive"))
    )
    (net (code "58") (name "Net-(R210-Pad1)") (class "Default")
      (node (ref "R210") (pin "1") (pinfunction "1_1") (pintype "passive"))
      (node (ref "U2") (pin "21") (pinfunction "NC_21") (pintype "passive"))
    )
    (net (code "59") (name "Net-(R211-Pad1)") (class "Default")
      (node (ref "R211") (pin "1") (pinfunction "1_1") (pintype "passive"))
      (node (ref "U2") (pin "20") (pinfunction "NC_20") (pintype "passive"))
    )
    (net (code "60") (name "Net-(RJ45-9)") (class "Default")
      (node (ref "R219") (pin "2") (pinfunction "2_2") (pintype "passive"))
      (node (ref "RJ45") (pin "A1") (pinfunction "9_A1") (pintype "passive"))
    )
    (net (code "61") (name "Net-(RJ45-12)") (class "Default")
      (node (ref "R220") (pin "2") (pinfunction "2_2") (pintype "passive"))
      (node (ref "RJ45") (pin "A2") (pinfunction "12_A2") (pintype "passive"))
    )
    (net (code "62") (name "Net-(U2-RBIAS)") (class "Default")
      (node (ref "R27") (pin "1") (pinfunction "1_1") (pintype "passive"))
      (node (ref "U2") (pin "24") (pinfunction "RBIAS_24") (pintype "passive"))
    )
    (net (code "63") (name "Net-(U12-~{HOLD})") (class "Default")
      (node (ref "R17") (pin "2") (pinfunction "2_2") (pintype "passive"))
      (node (ref "U12") (pin "7") (pinfunction "~{HOLD}_7") (pintype "passive"))
    )
    (net (code "64") (name "Net-(U12-~{WP})") (class "Default")
      (node (ref "R16") (pin "2") (pinfunction "2_2") (pintype "passive"))
      (node (ref "U12") (pin "3") (pinfunction "~{WP}_3") (pintype "passive"))
    )
    (net (code "65") (name "unconnected-(Power-Pad1)") (class "Default")
      (node (ref "Power") (pin "1") (pinfunction "1_1") (pintype "passive"))
    )
    (net (code "66") (name "unconnected-(Power-Pad2)") (class "Default")
      (node (ref "Power") (pin "2") (pinfunction "2_2") (pintype "passive"))
    )
    (net (code "67") (name "unconnected-(U2-NC-Pad8)") (class "Default")
      (node (ref "U2") (pin "8") (pinfunction "NC_8") (pintype "passive"))
    )
    (net (code "68") (name "unconnected-(U2-NC-Pad9)") (class "Default")
      (node (ref "U2") (pin "9") (pinfunction "NC_9") (pintype "passive"))
    )
    (net (code "69") (name "unconnected-(U2-NC-Pad10)") (class "Default")
      (node (ref "U2") (pin "10") (pinfunction "NC_10") (pintype "passive"))
    )
    (net (code "70") (name "unconnected-(U2-NC-Pad11)") (class "Default")
      (node (ref "U2") (pin "11") (pinfunction "NC_11") (pintype "passive"))
    )
    (net (code "71") (name "unconnected-(U2-NC-Pad12)") (class "Default")
      (node (ref "U2") (pin "12") (pinfunction "NC_12") (pintype "passive"))
    )
    (net (code "72") (name "unconnected-(U2-X2-Pad33)") (class "Default")
      (node (ref "U2") (pin "33") (pinfunction "X2_33") (pintype "output"))
    )
    (net (code "73") (name "unconnected-(U11-PA4-Pad20)") (class "Default")
      (node (ref "U11") (pin "20") (pinfunction "PA4_20") (pintype "bidirectional"))
    )
    (net (code "74") (name "unconnected-(U11-PA5-Pad21)") (class "Default")
      (node (ref "U11") (pin "21") (pinfunction "PA5_21") (pintype "bidirectional"))
    )
    (net (code "75") (name "unconnected-(U11-PA6-Pad22)") (class "Default")
      (node (ref "U11") (pin "22") (pinfunction "PA6_22") (pintype "bidirectional"))
    )
    (net (code "76") (name "unconnected-(U11-PA11-Pad44)") (class "Default")
      (node (ref "U11") (pin "44") (pinfunction "PA11_44") (pintype "bidirectional+no_connect"))
    )
    (net (code "77") (name "unconnected-(U11-PA12-Pad45)") (class "Default")
      (node (ref "U11") (pin "45") (pinfunction "PA12_45") (pintype "bidirectional+no_connect"))
    )
    (net (code "78") (name "unconnected-(U11-PA15{slash}JTDI-Pad50)") (class "Default")
      (node (ref "U11") (pin "50") (pinfunction "PA15/JTDI_50") (pintype "bidirectional+no_connect"))
    )
    (net (code "79") (name "unconnected-(U11-PB2{slash}BOOT1-Pad28)") (class "Default")
      (node (ref "U11") (pin "28") (pinfunction "PB2/BOOT1_28") (pintype "bidirectional"))
    )
    (net (code "80") (name "unconnected-(U11-PB3{slash}JTDO-Pad55)") (class "Default")
      (node (ref "U11") (pin "55") (pinfunction "PB3/JTDO_55") (pintype "bidirectional"))
    )
    (net (code "81") (name "unconnected-(U11-PB4{slash}JNTRST-Pad56)") (class "Default")
      (node (ref "U11") (pin "56") (pinfunction "PB4/JNTRST_56") (pintype "bidirectional"))
    )
    (net (code "82") (name "unconnected-(U11-PB5-Pad57)") (class "Default")
      (node (ref "U11") (pin "57") (pinfunction "PB5_57") (pintype "bidirectional"))
    )
    (net (code "83") (name "unconnected-(U11-PB6-Pad58)") (class "Default")
      (node (ref "U11") (pin "58") (pinfunction "PB6_58") (pintype "bidirectional"))
    )
    (net (code "84") (name "unconnected-(U11-PB7-Pad59)") (class "Default")
      (node (ref "U11") (pin "59") (pinfunction "PB7_59") (pintype "bidirectional"))
    )
    (net (code "85") (name "unconnected-(U11-PB9-Pad62)") (class "Default")
      (node (ref "U11") (pin "62") (pinfunction "PB9_62") (pintype "bidirectional"))
    )
    (net (code "86") (name "unconnected-(U11-PB14-Pad35)") (class "Default")
      (node (ref "U11") (pin "35") (pinfunction "PB14_35") (pintype "bidirectional"))
    )
    (net (code "87") (name "unconnected-(U11-PC0-Pad8)") (class "Default")
      (node (ref "U11") (pin "8") (pinfunction "PC0_8") (pintype "bidirectional"))
    )
    (net (code "88") (name "unconnected-(U11-PC13-TAMPER-RTC-Pad2)") (class "Default")
      (node (ref "U11") (pin "2") (pinfunction "PC13-TAMPER-RTC_2") (pintype "bidirectional+no_connect"))
    )
    (net (code "89") (name "unconnected-(U11-PC14-OSC32_IN-Pad3)") (class "Default")
      (node (ref "U11") (pin "3") (pinfunction "PC14-OSC32_IN_3") (pintype "bidirectional"))
    )
    (net (code "90") (name "unconnected-(U11-PC15-OSC32_OUT-Pad4)") (class "Default")
      (node (ref "U11") (pin "4") (pinfunction "PC15-OSC32_OUT_4") (pintype "bidirectional"))
    )
  )
)
